# 18_-WIFI_MODULE.net
KiCad netlist of a schematic drawn in Altium Designer
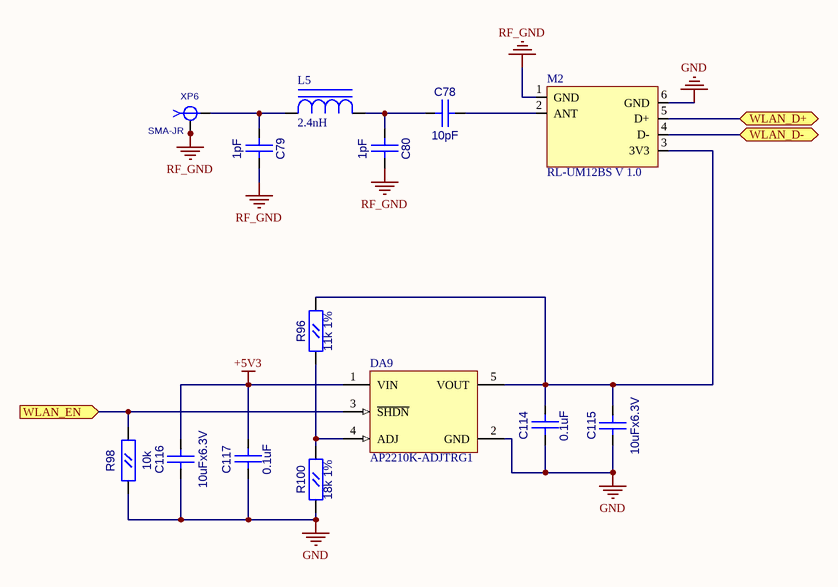
[diagram p0: [18]-WIFI_MODULE.SchDoc]

(export (version "E")
  (design (tool "Eeschema 10.0.6"))
  (components
    (comp (ref "C78")
      (value "10pF")
      (footprint "CC0603")
      (description "CC0603")
      (libsource (lib "gprs_modem_2") (part "CC0603"))
    )
    (comp (ref "C79")
      (value "1pF")
      (footprint "CC0603")
      (description "CC0603")
      (libsource (lib "gprs_modem_2") (part "CC0603"))
    )
    (comp (ref "C80")
      (value "1pF")
      (footprint "CC0603")
      (description "CC0603")
      (libsource (lib "gprs_modem_2") (part "CC0603"))
    )
    (comp (ref "C114")
      (value "0.1uF")
      (footprint "CC0603")
      (description "CC0603")
      (libsource (lib "gprs_modem_2") (part "CC0603"))
    )
    (comp (ref "C115")
      (value "10uFx6.3V")
      (footprint "CC0805")
      (description "CC0805")
      (libsource (lib "gprs_modem_2") (part "CC0805"))
    )
    (comp (ref "C116")
      (value "10uFx6.3V")
      (footprint "CC0805")
      (description "CC0805")
      (libsource (lib "gprs_modem_2") (part "CC0805"))
    )
    (comp (ref "C117")
      (value "0.1uF")
      (footprint "CC0603")
      (description "CC0603")
      (libsource (lib "gprs_modem_2") (part "CC0603"))
    )
    (comp (ref "DA9")
      (value "AP2210K-ADJTRG1")
      (footprint "SOT23-5")
      (fields (field (name "PUBLISHER") "Altium Limited"))
      (libsource (lib "gprs_modem_2") (part "MCP1824T-ADJE/OT"))
    )
    (comp (ref "L5")
      (value "2.4nH")
      (footprint "L0402")
      (description "L0402")
      (libsource (lib "gprs_modem_2") (part "L0402"))
    )
    (comp (ref "M2")
      (value "RL-UM12BS V 1.0")
      (footprint "RTL8188_MODULE")
      (libsource (lib "fizik_lib") (part "RTL8188_MODULE"))
    )
    (comp (ref "R96")
      (value "11k 1%")
      (footprint "RC0603")
      (description "RC0603")
      (libsource (lib "gprs_modem_2") (part "RC0603"))
    )
    (comp (ref "R98")
      (value "10k")
      (footprint "RC0603")
      (description "RC0603")
      (libsource (lib "gprs_modem_2") (part "RC0603"))
    )
    (comp (ref "R100")
      (value "18k 1%")
      (footprint "RC0603")
      (description "RC0603")
      (libsource (lib "gprs_modem_2") (part "RC0603"))
    )
    (comp (ref "XP6") (value "SMA-JR") (footprint "SMA-JR") (libsource (lib "fizik_lib") (part "SMA-JR")))
  )
  (nets
    (net (code "1") (name "+5V3") (class "Default")
      (node (ref "C116") (pin "2") (pinfunction "B_2") (pintype "passive"))
      (node (ref "C117") (pin "1") (pinfunction "A_1") (pintype "passive"))
      (node (ref "DA9") (pin "1") (pinfunction "VIN_1") (pintype "power_in"))
    )
    (net (code "2") (name "/WLAN_D+") (class "Default")
      (node (ref "M2") (pin "5") (pinfunction "D+_5") (pintype "passive"))
    )
    (net (code "3") (name "/WLAN_D-") (class "Default")
      (node (ref "M2") (pin "4") (pinfunction "D-_4") (pintype "passive"))
    )
    (net (code "4") (name "/WLAN_EN") (class "Default")
      (node (ref "DA9") (pin "3") (pinfunction "~{SHDN}_3") (pintype "input"))
      (node (ref "R98") (pin "2") (pinfunction "B_2") (pintype "passive"))
    )
    (net (code "5") (name "GND") (class "Default")
      (node (ref "C114") (pin "2") (pinfunction "B_2") (pintype "passive"))
      (node (ref "C115") (pin "1") (pinfunction "A_1") (pintype "passive"))
      (node (ref "C116") (pin "1") (pinfunction "A_1") (pintype "passive"))
      (node (ref "C117") (pin "2") (pinfunction "B_2") (pintype "passive"))
      (node (ref "DA9") (pin "2") (pinfunction "GND_2") (pintype "power_in"))
      (node (ref "M2") (pin "6") (pinfunction "GND_6") (pintype "passive"))
      (node (ref "R100") (pin "1") (pinfunction "A_1") (pintype "passive"))
      (node (ref "R98") (pin "1") (pinfunction "A_1") (pintype "passive"))
    )
    (net (code "6") (name "Net-(C78-A)") (class "Default")
      (node (ref "C78") (pin "1") (pinfunction "A_1") (pintype "passive"))
      (node (ref "C80") (pin "1") (pinfunction "A_1") (pintype "passive"))
      (node (ref "L5") (pin "2") (pinfunction "C_2") (pintype "passive"))
    )
    (net (code "7") (name "Net-(C78-B)") (class "Default")
      (node (ref "C78") (pin "2") (pinfunction "B_2") (pintype "passive"))
      (node (ref "M2") (pin "2") (pinfunction "ANT_2") (pintype "passive"))
    )
    (net (code "8") (name "Net-(C79-A)") (class "Default")
      (node (ref "C79") (pin "1") (pinfunction "A_1") (pintype "passive"))
      (node (ref "L5") (pin "1") (pinfunction "A_1") (pintype "passive"))
      (node (ref "XP6") (pin "1") (pintype "passive"))
    )
    (net (code "9") (name "Net-(C114-A)") (class "Default")
      (node (ref "C114") (pin "1") (pinfunction "A_1") (pintype "passive"))
      (node (ref "C115") (pin "2") (pinfunction "B_2") (pintype "passive"))
      (node (ref "DA9") (pin "5") (pinfunction "VOUT_5") (pintype "power_in"))
      (node (ref "M2") (pin "3") (pinfunction "3V3_3") (pintype "passive"))
      (node (ref "R96") (pin "2") (pinfunction "B_2") (pintype "passive"))
    )
    (net (code "10") (name "Net-(DA9-ADJ)") (class "Default")
      (node (ref "DA9") (pin "4") (pinfunction "ADJ_4") (pintype "input"))
      (node (ref "R100") (pin "2") (pinfunction "B_2") (pintype "passive"))
      (node (ref "R96") (pin "1") (pinfunction "A_1") (pintype "passive"))
    )
    (net (code "11") (name "RF_GND") (class "Default")
      (node (ref "C79") (pin "2") (pinfunction "B_2") (pintype "passive"))
      (node (ref "C80") (pin "2") (pinfunction "B_2") (pintype "passive"))
      (node (ref "M2") (pin "1") (pinfunction "GND_1") (pintype "passive"))
      (node (ref "XP6") (pin "2") (pintype "passive"))
      (node (ref "XP6") (pin "3") (pintype "passive"))
      (node (ref "XP6") (pin "4") (pintype "passive"))
      (node (ref "XP6") (pin "5") (pintype "passive"))
    )
  )
)
